# Adafruit_ESP8266_Feather.net
KiCad netlist of a schematic drawn in EAGLE
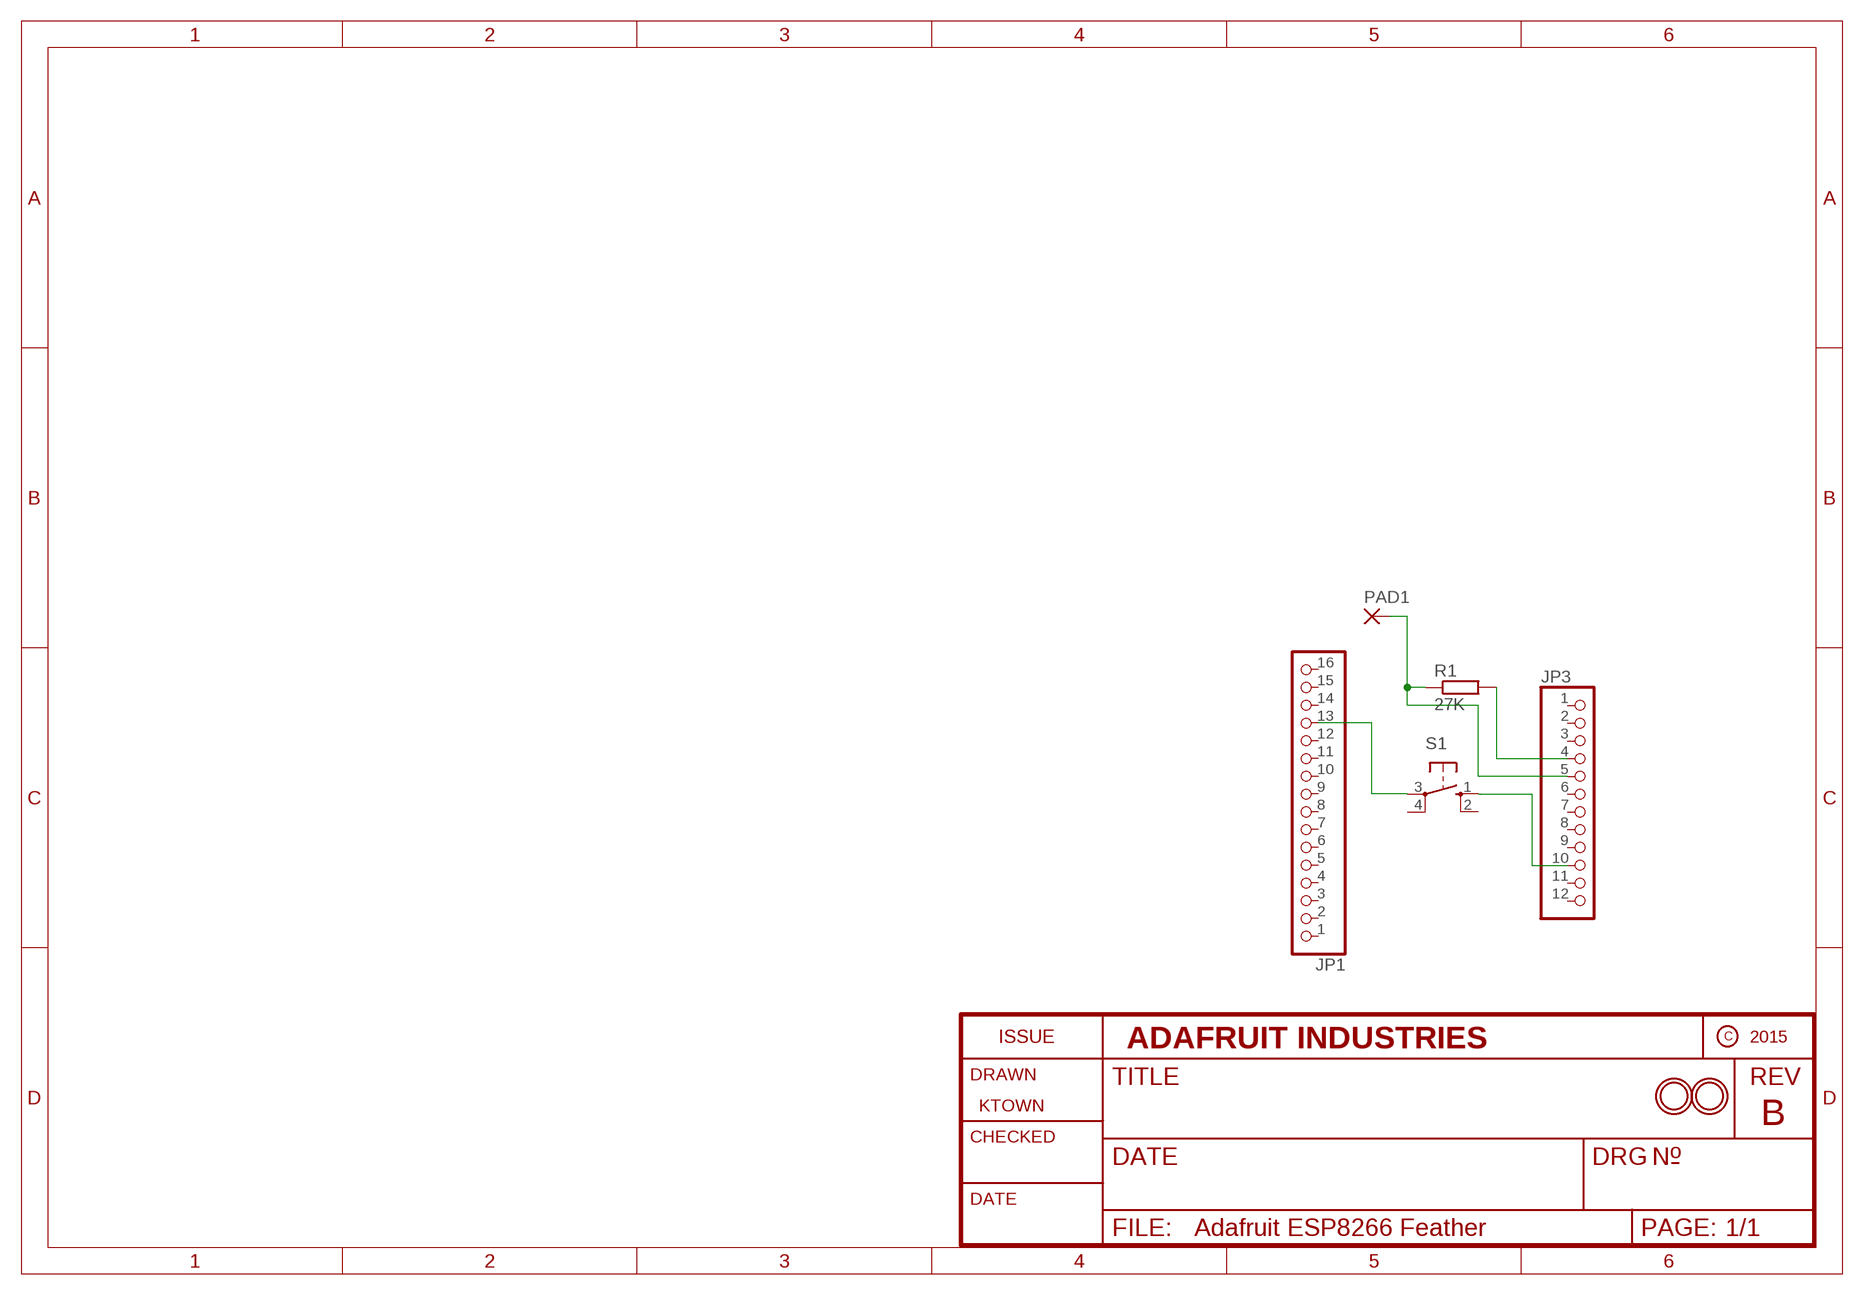
[diagram p0: schematic, sheet 1]

(export (version "E")
  (design (tool "Eeschema 10.0.6"))
  (components
    (comp (ref "JP1")
      (value "HEADER-1X16ROUND")
      (footprint "eagle-import:1X16_ROUND")
      (libsource (lib "eagle-import") (part "HEADER-1X16ROUND"))
    )
    (comp (ref "JP3")
      (value "HEADER-1X12")
      (footprint "eagle-import:1X12_ROUND")
      (libsource (lib "eagle-import") (part "HEADER-1X12"))
    )
    (comp (ref "PAD1")
      (value "1,6/0,9")
      (footprint "eagle-import:1,6_0,9")
      (libsource (lib "eagle-import") (part "1,6/0,9"))
    )
    (comp (ref "R1")
      (value "27K")
      (footprint "eagle-import:0207_10")
      (libsource (lib "eagle-import") (part "R-EU_0207/10"))
    )
    (comp (ref "S1")
      (value "10-XX")
      (footprint "eagle-import:B3F-10XX")
      (fields (field (name "MPN") "B3F-1000"))
      (libsource (lib "eagle-import") (part "10-XX"))
    )
    (comp (ref "U$31")
      (value "MOUNTINGHOLE2.5")
      (footprint "eagle-import:MOUNTINGHOLE_2.5_PLATED")
      (libsource (lib "eagle-import") (part "MOUNTINGHOLE2.5"))
    )
    (comp (ref "U$32")
      (value "MOUNTINGHOLE2.5")
      (footprint "eagle-import:MOUNTINGHOLE_2.5_PLATED")
      (libsource (lib "eagle-import") (part "MOUNTINGHOLE2.5"))
    )
  )
  (nets
    (net (code "1") (name "Net-(JP3-Pad4)") (class "Default")
      (node (ref "JP3") (pin "4") (pinfunction "4_4") (pintype "passive"))
      (node (ref "R1") (pin "2") (pinfunction "2_2") (pintype "passive"))
    )
    (net (code "2") (name "Net-(PAD1-P)") (class "Default")
      (node (ref "JP3") (pin "5") (pinfunction "5_5") (pintype "passive"))
      (node (ref "PAD1") (pin "1") (pinfunction "P_1") (pintype "passive"))
      (node (ref "R1") (pin "1") (pinfunction "1_1") (pintype "passive"))
    )
    (net (code "3") (name "Net-(S1-P)") (class "Default")
      (node (ref "JP1") (pin "13") (pinfunction "13_13") (pintype "passive"))
      (node (ref "S1") (pin "3") (pinfunction "P_3") (pintype "passive"))
    )
    (net (code "4") (name "Net-(S1-S)") (class "Default")
      (node (ref "JP3") (pin "10") (pinfunction "10_10") (pintype "passive"))
      (node (ref "S1") (pin "1") (pinfunction "S_1") (pintype "passive"))
    )
    (net (code "5") (name "unconnected-(JP1-Pad1)") (class "Default")
      (node (ref "JP1") (pin "1") (pinfunction "1_1") (pintype "passive"))
    )
    (net (code "6") (name "unconnected-(JP1-Pad2)") (class "Default")
      (node (ref "JP1") (pin "2") (pinfunction "2_2") (pintype "passive"))
    )
    (net (code "7") (name "unconnected-(JP1-Pad3)") (class "Default")
      (node (ref "JP1") (pin "3") (pinfunction "3_3") (pintype "passive"))
    )
    (net (code "8") (name "unconnected-(JP1-Pad4)") (class "Default")
      (node (ref "JP1") (pin "4") (pinfunction "4_4") (pintype "passive"))
    )
    (net (code "9") (name "unconnected-(JP1-Pad5)") (class "Default")
      (node (ref "JP1") (pin "5") (pinfunction "5_5") (pintype "passive"))
    )
    (net (code "10") (name "unconnected-(JP1-Pad6)") (class "Default")
      (node (ref "JP1") (pin "6") (pinfunction "6_6") (pintype "passive"))
    )
    (net (code "11") (name "unconnected-(JP1-Pad7)") (class "Default")
      (node (ref "JP1") (pin "7") (pinfunction "7_7") (pintype "passive"))
    )
    (net (code "12") (name "unconnected-(JP1-Pad8)") (class "Default")
      (node (ref "JP1") (pin "8") (pinfunction "8_8") (pintype "passive"))
    )
    (net (code "13") (name "unconnected-(JP1-Pad9)") (class "Default")
      (node (ref "JP1") (pin "9") (pinfunction "9_9") (pintype "passive"))
    )
    (net (code "14") (name "unconnected-(JP1-Pad10)") (class "Default")
      (node (ref "JP1") (pin "10") (pinfunction "10_10") (pintype "passive"))
    )
    (net (code "15") (name "unconnected-(JP1-Pad11)") (class "Default")
      (node (ref "JP1") (pin "11") (pinfunction "11_11") (pintype "passive"))
    )
    (net (code "16") (name "unconnected-(JP1-Pad12)") (class "Default")
      (node (ref "JP1") (pin "12") (pinfunction "12_12") (pintype "passive"))
    )
    (net (code "17") (name "unconnected-(JP1-Pad14)") (class "Default")
      (node (ref "JP1") (pin "14") (pinfunction "14_14") (pintype "passive"))
    )
    (net (code "18") (name "unconnected-(JP1-Pad15)") (class "Default")
      (node (ref "JP1") (pin "15") (pinfunction "15_15") (pintype "passive"))
    )
    (net (code "19") (name "unconnected-(JP1-Pad16)") (class "Default")
      (node (ref "JP1") (pin "16") (pinfunction "16_16") (pintype "passive"))
    )
    (net (code "20") (name "unconnected-(JP3-Pad1)") (class "Default")
      (node (ref "JP3") (pin "1") (pinfunction "1_1") (pintype "passive"))
    )
    (net (code "21") (name "unconnected-(JP3-Pad2)") (class "Default")
      (node (ref "JP3") (pin "2") (pinfunction "2_2") (pintype "passive"))
    )
    (net (code "22") (name "unconnected-(JP3-Pad3)") (class "Default")
      (node (ref "JP3") (pin "3") (pinfunction "3_3") (pintype "passive"))
    )
    (net (code "23") (name "unconnected-(JP3-Pad6)") (class "Default")
      (node (ref "JP3") (pin "6") (pinfunction "6_6") (pintype "passive"))
    )
    (net (code "24") (name "unconnected-(JP3-Pad7)") (class "Default")
      (node (ref "JP3") (pin "7") (pinfunction "7_7") (pintype "passive"))
    )
    (net (code "25") (name "unconnected-(JP3-Pad8)") (class "Default")
      (node (ref "JP3") (pin "8") (pinfunction "8_8") (pintype "passive"))
    )
    (net (code "26") (name "unconnected-(JP3-Pad9)") (class "Default")
      (node (ref "JP3") (pin "9") (pinfunction "9_9") (pintype "passive"))
    )
    (net (code "27") (name "unconnected-(JP3-Pad11)") (class "Default")
      (node (ref "JP3") (pin "11") (pinfunction "11_11") (pintype "passive"))
    )
    (net (code "28") (name "unconnected-(JP3-Pad12)") (class "Default")
      (node (ref "JP3") (pin "12") (pinfunction "12_12") (pintype "passive"))
    )
    (net (code "29") (name "unconnected-(S1-P1-Pad4)") (class "Default")
      (node (ref "S1") (pin "4") (pinfunction "P1_4") (pintype "passive"))
    )
    (net (code "30") (name "unconnected-(S1-S1-Pad2)") (class "Default")
      (node (ref "S1") (pin "2") (pinfunction "S1_2") (pintype "passive"))
    )
  )
)
